# ANSI_Mono_vid_board.net
KiCad netlist of a schematic drawn in EAGLE
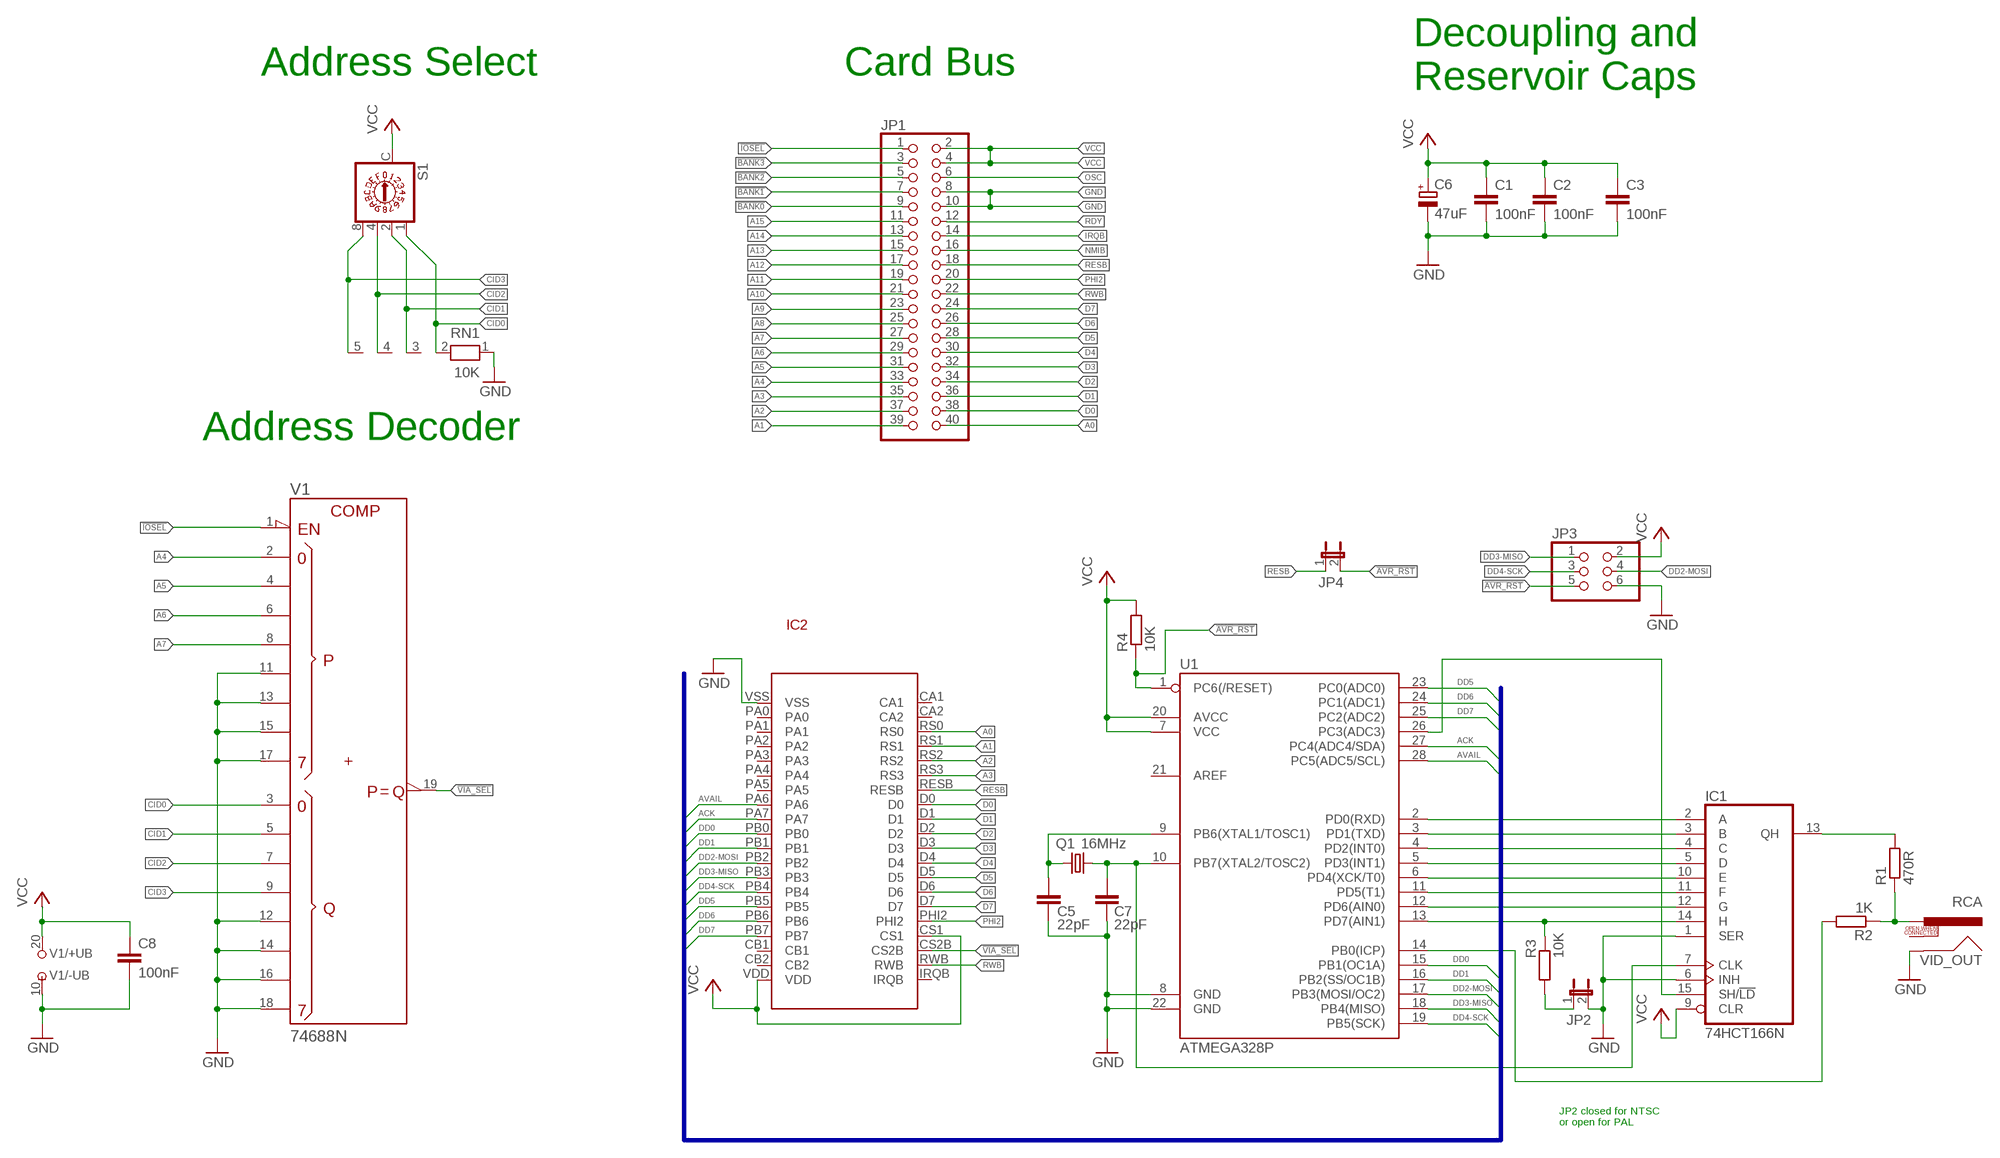
[diagram p0: schematic, sheet 1]

(export (version "E")
  (design (tool "Eeschema 10.0.6"))
  (components
    (comp (ref "C1")
      (value "100nF")
      (footprint "eagle-import:C050-025X075")
      (libsource (lib "eagle-import") (part "C-EU050-025X075"))
    )
    (comp (ref "C2")
      (value "100nF")
      (footprint "eagle-import:C050-025X075")
      (libsource (lib "eagle-import") (part "C-EU050-025X075"))
    )
    (comp (ref "C3")
      (value "100nF")
      (footprint "eagle-import:C025-025X050")
      (libsource (lib "eagle-import") (part "C-EU025-025X050"))
    )
    (comp (ref "C5")
      (value "22pF")
      (footprint "eagle-import:C050-025X075")
      (libsource (lib "eagle-import") (part "C-EU050-025X075"))
    )
    (comp (ref "C6")
      (value "47uF")
      (footprint "eagle-import:E2,5-7")
      (libsource (lib "eagle-import") (part "CPOL-EUE2.5-7"))
    )
    (comp (ref "C7")
      (value "22pF")
      (footprint "eagle-import:C050-025X075")
      (libsource (lib "eagle-import") (part "C-EU050-025X075"))
    )
    (comp (ref "C8")
      (value "100nF")
      (footprint "eagle-import:C050-025X075")
      (libsource (lib "eagle-import") (part "C-EU050-025X075"))
    )
    (comp (ref "IC1")
      (value "74HCT166N")
      (footprint "eagle-import:DIL16")
      (libsource (lib "eagle-import") (part "74166NHCT"))
    )
    (comp (ref "IC2")
      (value "W65C22")
      (footprint "eagle-import:W65C22-DIP")
      (libsource (lib "eagle-import") (part "W65C22"))
    )
    (comp (ref "JP1")
      (value "PINHD-2X20/90")
      (footprint "eagle-import:2X20_90")
      (libsource (lib "eagle-import") (part "PINHD-2X20/90"))
    )
    (comp (ref "JP2")
      (value "JP1E")
      (footprint "eagle-import:JP1")
      (libsource (lib "eagle-import") (part "JP1E"))
    )
    (comp (ref "JP3")
      (value "PINHD-2X3")
      (footprint "eagle-import:2X03")
      (libsource (lib "eagle-import") (part "PINHD-2X3"))
    )
    (comp (ref "JP4")
      (value "JP1E")
      (footprint "eagle-import:JP1")
      (libsource (lib "eagle-import") (part "JP1E"))
    )
    (comp (ref "Q1")
      (value "16MHz")
      (footprint "eagle-import:HC49U-V")
      (libsource (lib "eagle-import") (part "CRYSTALHC49U-V"))
    )
    (comp (ref "R1")
      (value "470R")
      (footprint "eagle-import:0207_10")
      (libsource (lib "eagle-import") (part "R-EU_0207/10"))
    )
    (comp (ref "R2")
      (value "1K")
      (footprint "eagle-import:0207_10")
      (libsource (lib "eagle-import") (part "R-EU_0207/10"))
    )
    (comp (ref "R3")
      (value "10K")
      (footprint "eagle-import:0207_2V")
      (libsource (lib "eagle-import") (part "R-EU_0207/2V"))
    )
    (comp (ref "R4")
      (value "10K")
      (footprint "eagle-import:0207_7")
      (libsource (lib "eagle-import") (part "R-EU_0207/7"))
    )
    (comp (ref "RN1")
      (value "10K")
      (footprint "eagle-import:RN-5")
      (libsource (lib "eagle-import") (part "RN04"))
    )
    (comp (ref "S1")
      (value "DRR3016")
      (footprint "eagle-import:DRR3010")
      (libsource (lib "eagle-import") (part "DRR3016"))
    )
    (comp (ref "U1")
      (value "ATMEGA328P")
      (footprint "eagle-import:DIL28-3")
      (libsource (lib "eagle-import") (part "ATMEGA328P_PDIP"))
    )
    (comp (ref "V1")
      (value "74688N")
      (footprint "eagle-import:DIL20")
      (libsource (lib "eagle-import") (part "74688N"))
    )
    (comp (ref "VID_OUT")
      (value "RCA")
      (footprint "eagle-import:RCA")
      (libsource (lib "eagle-import") (part "RCA"))
    )
  )
  (nets
    (net (code "1") (name "/ACK") (class "Default")
      (node (ref "IC2") (pin "PA7") (pinfunction "PA7_PA7") (pintype "bidirectional"))
      (node (ref "U1") (pin "27") (pinfunction "PC4(ADC4/SDA)_27") (pintype "bidirectional"))
    )
    (net (code "2") (name "/AVAIL") (class "Default")
      (node (ref "IC2") (pin "PA6") (pinfunction "PA6_PA6") (pintype "bidirectional"))
      (node (ref "U1") (pin "28") (pinfunction "PC5(ADC5/SCL)_28") (pintype "bidirectional"))
    )
    (net (code "3") (name "/DD0") (class "Default")
      (node (ref "IC2") (pin "PB0") (pinfunction "PB0_PB0") (pintype "bidirectional"))
      (node (ref "U1") (pin "15") (pinfunction "PB1(OC1A)_15") (pintype "bidirectional"))
    )
    (net (code "4") (name "/DD1") (class "Default")
      (node (ref "IC2") (pin "PB1") (pinfunction "PB1_PB1") (pintype "bidirectional"))
      (node (ref "U1") (pin "16") (pinfunction "PB2(SS/OC1B)_16") (pintype "bidirectional"))
    )
    (net (code "5") (name "/DD5") (class "Default")
      (node (ref "IC2") (pin "PB5") (pinfunction "PB5_PB5") (pintype "bidirectional"))
      (node (ref "U1") (pin "23") (pinfunction "PC0(ADC0)_23") (pintype "bidirectional"))
    )
    (net (code "6") (name "/DD6") (class "Default")
      (node (ref "IC2") (pin "PB6") (pinfunction "PB6_PB6") (pintype "bidirectional"))
      (node (ref "U1") (pin "24") (pinfunction "PC1(ADC1)_24") (pintype "bidirectional"))
    )
    (net (code "7") (name "/DD7") (class "Default")
      (node (ref "IC2") (pin "PB7") (pinfunction "PB7_PB7") (pintype "bidirectional"))
      (node (ref "U1") (pin "25") (pinfunction "PC2(ADC2)_25") (pintype "bidirectional"))
    )
    (net (code "8") (name "/~{AVR_RST}") (class "Default")
      (node (ref "JP3") (pin "5") (pinfunction "5_5") (pintype "passive"))
      (node (ref "JP4") (pin "2") (pinfunction "2_2") (pintype "passive"))
      (node (ref "R4") (pin "1") (pinfunction "1_1") (pintype "passive"))
      (node (ref "U1") (pin "1") (pinfunction "PC6(/RESET)_1") (pintype "bidirectional"))
    )
    (net (code "9") (name "/~{BANK0}") (class "Default")
      (node (ref "JP1") (pin "9") (pinfunction "9_9") (pintype "passive"))
    )
    (net (code "10") (name "/~{BANK1}") (class "Default")
      (node (ref "JP1") (pin "7") (pinfunction "7_7") (pintype "passive"))
    )
    (net (code "11") (name "/~{BANK2}") (class "Default")
      (node (ref "JP1") (pin "5") (pinfunction "5_5") (pintype "passive"))
    )
    (net (code "12") (name "/~{BANK3}") (class "Default")
      (node (ref "JP1") (pin "3") (pinfunction "3_3") (pintype "passive"))
    )
    (net (code "13") (name "/~{IOSEL}") (class "Default")
      (node (ref "JP1") (pin "1") (pinfunction "1_1") (pintype "passive"))
      (node (ref "V1") (pin "1") (pinfunction "~{G}_1") (pintype "input"))
    )
    (net (code "14") (name "/~{VIA_SEL}") (class "Default")
      (node (ref "IC2") (pin "CS2B") (pinfunction "CS2B_CS2B") (pintype "bidirectional"))
      (node (ref "V1") (pin "19") (pinfunction "~{P=Q}_19") (pintype "output"))
    )
    (net (code "15") (name "A0") (class "Default")
      (node (ref "IC2") (pin "RS0") (pinfunction "RS0_RS0") (pintype "input"))
      (node (ref "JP1") (pin "40") (pinfunction "40_40") (pintype "passive"))
    )
    (net (code "16") (name "A1") (class "Default")
      (node (ref "IC2") (pin "RS1") (pinfunction "RS1_RS1") (pintype "input"))
      (node (ref "JP1") (pin "39") (pinfunction "39_39") (pintype "passive"))
    )
    (net (code "17") (name "A2") (class "Default")
      (node (ref "IC2") (pin "RS2") (pinfunction "RS2_RS2") (pintype "input"))
      (node (ref "JP1") (pin "37") (pinfunction "37_37") (pintype "passive"))
    )
    (net (code "18") (name "A3") (class "Default")
      (node (ref "IC2") (pin "RS3") (pinfunction "RS3_RS3") (pintype "input"))
      (node (ref "JP1") (pin "35") (pinfunction "35_35") (pintype "passive"))
    )
    (net (code "19") (name "A4") (class "Default")
      (node (ref "JP1") (pin "33") (pinfunction "33_33") (pintype "passive"))
      (node (ref "V1") (pin "2") (pinfunction "P0_2") (pintype "input"))
    )
    (net (code "20") (name "A5") (class "Default")
      (node (ref "JP1") (pin "31") (pinfunction "31_31") (pintype "passive"))
      (node (ref "V1") (pin "4") (pinfunction "P1_4") (pintype "input"))
    )
    (net (code "21") (name "A6") (class "Default")
      (node (ref "JP1") (pin "29") (pinfunction "29_29") (pintype "passive"))
      (node (ref "V1") (pin "6") (pinfunction "P2_6") (pintype "input"))
    )
    (net (code "22") (name "A7") (class "Default")
      (node (ref "JP1") (pin "27") (pinfunction "27_27") (pintype "passive"))
      (node (ref "V1") (pin "8") (pinfunction "P3_8") (pintype "input"))
    )
    (net (code "23") (name "A8") (class "Default")
      (node (ref "JP1") (pin "25") (pinfunction "25_25") (pintype "passive"))
    )
    (net (code "24") (name "A9") (class "Default")
      (node (ref "JP1") (pin "23") (pinfunction "23_23") (pintype "passive"))
    )
    (net (code "25") (name "A10") (class "Default")
      (node (ref "JP1") (pin "21") (pinfunction "21_21") (pintype "passive"))
    )
    (net (code "26") (name "A11") (class "Default")
      (node (ref "JP1") (pin "19") (pinfunction "19_19") (pintype "passive"))
    )
    (net (code "27") (name "A12") (class "Default")
      (node (ref "JP1") (pin "17") (pinfunction "17_17") (pintype "passive"))
    )
    (net (code "28") (name "A13") (class "Default")
      (node (ref "JP1") (pin "15") (pinfunction "15_15") (pintype "passive"))
    )
    (net (code "29") (name "A14") (class "Default")
      (node (ref "JP1") (pin "13") (pinfunction "13_13") (pintype "passive"))
    )
    (net (code "30") (name "A15") (class "Default")
      (node (ref "JP1") (pin "11") (pinfunction "11_11") (pintype "passive"))
    )
    (net (code "31") (name "CID0") (class "Default")
      (node (ref "RN1") (pin "2") (pinfunction "2_2") (pintype "passive"))
      (node (ref "S1") (pin "1") (pinfunction "1_1") (pintype "passive"))
      (node (ref "V1") (pin "3") (pinfunction "Q0_3") (pintype "input"))
    )
    (net (code "32") (name "CID1") (class "Default")
      (node (ref "RN1") (pin "3") (pinfunction "3_3") (pintype "passive"))
      (node (ref "S1") (pin "2") (pinfunction "2_2") (pintype "passive"))
      (node (ref "V1") (pin "5") (pinfunction "Q1_5") (pintype "input"))
    )
    (net (code "33") (name "CID2") (class "Default")
      (node (ref "RN1") (pin "4") (pinfunction "4_4") (pintype "passive"))
      (node (ref "S1") (pin "4") (pinfunction "4_4") (pintype "passive"))
      (node (ref "V1") (pin "7") (pinfunction "Q2_7") (pintype "input"))
    )
    (net (code "34") (name "CID3") (class "Default")
      (node (ref "RN1") (pin "5") (pinfunction "5_5") (pintype "passive"))
      (node (ref "S1") (pin "8") (pinfunction "8_8") (pintype "passive"))
      (node (ref "V1") (pin "9") (pinfunction "Q3_9") (pintype "input"))
    )
    (net (code "35") (name "D0") (class "Default")
      (node (ref "IC2") (pin "D0") (pinfunction "D0_D0") (pintype "bidirectional"))
      (node (ref "JP1") (pin "38") (pinfunction "38_38") (pintype "passive"))
    )
    (net (code "36") (name "D1") (class "Default")
      (node (ref "IC2") (pin "D1") (pinfunction "D1_D1") (pintype "bidirectional"))
      (node (ref "JP1") (pin "36") (pinfunction "36_36") (pintype "passive"))
    )
    (net (code "37") (name "D2") (class "Default")
      (node (ref "IC2") (pin "D2") (pinfunction "D2_D2") (pintype "bidirectional"))
      (node (ref "JP1") (pin "34") (pinfunction "34_34") (pintype "passive"))
    )
    (net (code "38") (name "D3") (class "Default")
      (node (ref "IC2") (pin "D3") (pinfunction "D3_D3") (pintype "bidirectional"))
      (node (ref "JP1") (pin "32") (pinfunction "32_32") (pintype "passive"))
    )
    (net (code "39") (name "D4") (class "Default")
      (node (ref "IC2") (pin "D4") (pinfunction "D4_D4") (pintype "bidirectional"))
      (node (ref "JP1") (pin "30") (pinfunction "30_30") (pintype "passive"))
    )
    (net (code "40") (name "D5") (class "Default")
      (node (ref "IC2") (pin "D5") (pinfunction "D5_D5") (pintype "bidirectional"))
      (node (ref "JP1") (pin "28") (pinfunction "28_28") (pintype "passive"))
    )
    (net (code "41") (name "D6") (class "Default")
      (node (ref "IC2") (pin "D6") (pinfunction "D6_D6") (pintype "bidirectional"))
      (node (ref "JP1") (pin "26") (pinfunction "26_26") (pintype "passive"))
    )
    (net (code "42") (name "D7") (class "Default")
      (node (ref "IC2") (pin "D7") (pinfunction "D7_D7") (pintype "bidirectional"))
      (node (ref "JP1") (pin "24") (pinfunction "24_24") (pintype "passive"))
    )
    (net (code "43") (name "DD2-MOSI") (class "Default")
      (node (ref "IC2") (pin "PB2") (pinfunction "PB2_PB2") (pintype "bidirectional"))
      (node (ref "JP3") (pin "4") (pinfunction "4_4") (pintype "passive"))
      (node (ref "U1") (pin "17") (pinfunction "PB3(MOSI/OC2)_17") (pintype "bidirectional"))
    )
    (net (code "44") (name "DD3-MISO") (class "Default")
      (node (ref "IC2") (pin "PB3") (pinfunction "PB3_PB3") (pintype "bidirectional"))
      (node (ref "JP3") (pin "1") (pinfunction "1_1") (pintype "passive"))
      (node (ref "U1") (pin "18") (pinfunction "PB4(MISO)_18") (pintype "bidirectional"))
    )
    (net (code "45") (name "DD4-SCK") (class "Default")
      (node (ref "IC2") (pin "PB4") (pinfunction "PB4_PB4") (pintype "bidirectional"))
      (node (ref "JP3") (pin "3") (pinfunction "3_3") (pintype "passive"))
      (node (ref "U1") (pin "19") (pinfunction "PB5(SCK)_19") (pintype "bidirectional"))
    )
    (net (code "46") (name "GND") (class "Default")
      (node (ref "C1") (pin "2") (pinfunction "2_2") (pintype "passive"))
      (node (ref "C2") (pin "2") (pinfunction "2_2") (pintype "passive"))
      (node (ref "C3") (pin "2") (pinfunction "2_2") (pintype "passive"))
      (node (ref "C5") (pin "2") (pinfunction "2_2") (pintype "passive"))
      (node (ref "C6") (pin "-") (pinfunction "-_-") (pintype "passive"))
      (node (ref "C7") (pin "2") (pinfunction "2_2") (pintype "passive"))
      (node (ref "C8") (pin "2") (pinfunction "2_2") (pintype "passive"))
      (node (ref "IC1") (pin "1") (pinfunction "SER_1") (pintype "input"))
      (node (ref "IC1") (pin "6") (pinfunction "INH_6") (pintype "input"))
      (node (ref "IC2") (pin "VSS") (pinfunction "VSS_VSS") (pintype "power_in"))
      (node (ref "JP1") (pin "10") (pinfunction "10_10") (pintype "passive"))
      (node (ref "JP1") (pin "8") (pinfunction "8_8") (pintype "passive"))
      (node (ref "JP2") (pin "2") (pinfunction "2_2") (pintype "passive"))
      (node (ref "JP3") (pin "6") (pinfunction "6_6") (pintype "passive"))
      (node (ref "RN1") (pin "1") (pinfunction "1_1") (pintype "passive"))
      (node (ref "U1") (pin "22") (pinfunction "GND_22") (pintype "bidirectional"))
      (node (ref "U1") (pin "8") (pinfunction "GND_8") (pintype "bidirectional"))
      (node (ref "V1") (pin "10") (pinfunction "-UB_10") (pintype "power_in"))
      (node (ref "V1") (pin "11") (pinfunction "P4_11") (pintype "input"))
      (node (ref "V1") (pin "12") (pinfunction "Q4_12") (pintype "input"))
      (node (ref "V1") (pin "13") (pinfunction "P5_13") (pintype "input"))
      (node (ref "V1") (pin "14") (pinfunction "Q5_14") (pintype "input"))
      (node (ref "V1") (pin "15") (pinfunction "P6_15") (pintype "input"))
      (node (ref "V1") (pin "16") (pinfunction "Q6_16") (pintype "input"))
      (node (ref "V1") (pin "17") (pinfunction "P7_17") (pintype "input"))
      (node (ref "V1") (pin "18") (pinfunction "Q7_18") (pintype "input"))
      (node (ref "VID_OUT") (pin "SHELL") (pinfunction "SHELL_SHELL") (pintype "bidirectional"))
    )
    (net (code "47") (name "IRQB") (class "Default")
      (node (ref "JP1") (pin "14") (pinfunction "14_14") (pintype "passive"))
    )
    (net (code "48") (name "NMIB") (class "Default")
      (node (ref "JP1") (pin "16") (pinfunction "16_16") (pintype "passive"))
    )
    (net (code "49") (name "Net-(IC1A-A)") (class "Default")
      (node (ref "IC1") (pin "2") (pinfunction "A_2") (pintype "input"))
      (node (ref "U1") (pin "2") (pinfunction "PD0(RXD)_2") (pintype "bidirectional"))
    )
    (net (code "50") (name "Net-(IC1A-B)") (class "Default")
      (node (ref "IC1") (pin "3") (pinfunction "B_3") (pintype "input"))
      (node (ref "U1") (pin "3") (pinfunction "PD1(TXD)_3") (pintype "bidirectional"))
    )
    (net (code "51") (name "Net-(IC1A-C)") (class "Default")
      (node (ref "IC1") (pin "4") (pinfunction "C_4") (pintype "input"))
      (node (ref "U1") (pin "4") (pinfunction "PD2(INT0)_4") (pintype "bidirectional"))
    )
    (net (code "52") (name "Net-(IC1A-CLK)") (class "Default")
      (node (ref "C7") (pin "1") (pinfunction "1_1") (pintype "passive"))
      (node (ref "IC1") (pin "7") (pinfunction "CLK_7") (pintype "input"))
      (node (ref "Q1") (pin "1") (pinfunction "1_1") (pintype "passive"))
      (node (ref "U1") (pin "10") (pinfunction "PB7(XTAL2/TOSC2)_10") (pintype "bidirectional"))
    )
    (net (code "53") (name "Net-(IC1A-D)") (class "Default")
      (node (ref "IC1") (pin "5") (pinfunction "D_5") (pintype "input"))
      (node (ref "U1") (pin "5") (pinfunction "PD3(INT1)_5") (pintype "bidirectional"))
    )
    (net (code "54") (name "Net-(IC1A-E)") (class "Default")
      (node (ref "IC1") (pin "10") (pinfunction "E_10") (pintype "input"))
      (node (ref "U1") (pin "6") (pinfunction "PD4(XCK/T0)_6") (pintype "bidirectional"))
    )
    (net (code "55") (name "Net-(IC1A-F)") (class "Default")
      (node (ref "IC1") (pin "11") (pinfunction "F_11") (pintype "input"))
      (node (ref "U1") (pin "11") (pinfunction "PD5(T1)_11") (pintype "bidirectional"))
    )
    (net (code "56") (name "Net-(IC1A-G)") (class "Default")
      (node (ref "IC1") (pin "12") (pinfunction "G_12") (pintype "input"))
      (node (ref "U1") (pin "12") (pinfunction "PD6(AIN0)_12") (pintype "bidirectional"))
    )
    (net (code "57") (name "Net-(IC1A-H)") (class "Default")
      (node (ref "IC1") (pin "14") (pinfunction "H_14") (pintype "input"))
      (node (ref "R3") (pin "2") (pinfunction "2_2") (pintype "passive"))
      (node (ref "U1") (pin "13") (pinfunction "PD7(AIN1)_13") (pintype "bidirectional"))
    )
    (net (code "58") (name "Net-(IC1A-QH)") (class "Default")
      (node (ref "IC1") (pin "13") (pinfunction "QH_13") (pintype "output"))
      (node (ref "R1") (pin "2") (pinfunction "2_2") (pintype "passive"))
    )
    (net (code "59") (name "Net-(IC1A-SH{slash}~{LD})") (class "Default")
      (node (ref "IC1") (pin "15") (pinfunction "SH/~{LD}_15") (pintype "input"))
      (node (ref "U1") (pin "26") (pinfunction "PC3(ADC3)_26") (pintype "bidirectional"))
    )
    (net (code "60") (name "Net-(JP2-Pad1)") (class "Default")
      (node (ref "JP2") (pin "1") (pinfunction "1_1") (pintype "passive"))
      (node (ref "R3") (pin "1") (pinfunction "1_1") (pintype "passive"))
    )
    (net (code "61") (name "Net-(R1-Pad1)") (class "Default")
      (node (ref "R1") (pin "1") (pinfunction "1_1") (pintype "passive"))
      (node (ref "R2") (pin "1") (pinfunction "1_1") (pintype "passive"))
      (node (ref "VID_OUT") (pin "PIN") (pinfunction "PIN_PIN") (pintype "bidirectional"))
    )
    (net (code "62") (name "Net-(U1-PB0(ICP))") (class "Default")
      (node (ref "R2") (pin "2") (pinfunction "2_2") (pintype "passive"))
      (node (ref "U1") (pin "14") (pinfunction "PB0(ICP)_14") (pintype "bidirectional"))
    )
    (net (code "63") (name "Net-(U1-PB6(XTAL1{slash}TOSC1))") (class "Default")
      (node (ref "C5") (pin "1") (pinfunction "1_1") (pintype "passive"))
      (node (ref "Q1") (pin "2") (pinfunction "2_2") (pintype "passive"))
      (node (ref "U1") (pin "9") (pinfunction "PB6(XTAL1/TOSC1)_9") (pintype "bidirectional"))
    )
    (net (code "64") (name "OSC") (class "Default")
      (node (ref "JP1") (pin "6") (pinfunction "6_6") (pintype "passive"))
    )
    (net (code "65") (name "PHI2") (class "Default")
      (node (ref "IC2") (pin "PHI2") (pinfunction "PHI2_PHI2") (pintype "input"))
      (node (ref "JP1") (pin "20") (pinfunction "20_20") (pintype "passive"))
    )
    (net (code "66") (name "RDY") (class "Default")
      (node (ref "JP1") (pin "12") (pinfunction "12_12") (pintype "passive"))
    )
    (net (code "67") (name "RESB") (class "Default")
      (node (ref "IC2") (pin "RESB") (pinfunction "RESB_RESB") (pintype "input"))
      (node (ref "JP1") (pin "18") (pinfunction "18_18") (pintype "passive"))
      (node (ref "JP4") (pin "1") (pinfunction "1_1") (pintype "passive"))
    )
    (net (code "68") (name "RWB") (class "Default")
      (node (ref "IC2") (pin "RWB") (pinfunction "RWB_RWB") (pintype "input"))
      (node (ref "JP1") (pin "22") (pinfunction "22_22") (pintype "passive"))
    )
    (net (code "69") (name "VCC") (class "Default")
      (node (ref "C1") (pin "1") (pinfunction "1_1") (pintype "passive"))
      (node (ref "C2") (pin "1") (pinfunction "1_1") (pintype "passive"))
      (node (ref "C3") (pin "1") (pinfunction "1_1") (pintype "passive"))
      (node (ref "C6") (pin "+") (pinfunction "+_+") (pintype "passive"))
      (node (ref "C8") (pin "1") (pinfunction "1_1") (pintype "passive"))
      (node (ref "IC1") (pin "9") (pinfunction "CLR_9") (pintype "input"))
      (node (ref "IC2") (pin "CS1") (pinfunction "CS1_CS1") (pintype "bidirectional"))
      (node (ref "IC2") (pin "VDD") (pinfunction "VDD_VDD") (pintype "power_in"))
      (node (ref "JP1") (pin "2") (pinfunction "2_2") (pintype "passive"))
      (node (ref "JP1") (pin "4") (pinfunction "4_4") (pintype "passive"))
      (node (ref "JP3") (pin "2") (pinfunction "2_2") (pintype "passive"))
      (node (ref "R4") (pin "2") (pinfunction "2_2") (pintype "passive"))
      (node (ref "S1") (pin "C") (pinfunction "C_C") (pintype "passive"))
      (node (ref "U1") (pin "20") (pinfunction "AVCC_20") (pintype "bidirectional"))
      (node (ref "U1") (pin "7") (pinfunction "VCC_7") (pintype "bidirectional"))
      (node (ref "V1") (pin "20") (pinfunction "+UB_20") (pintype "power_in"))
    )
    (net (code "70") (name "unconnected-(IC2-PadCA1)") (class "Default")
      (node (ref "IC2") (pin "CA1") (pinfunction "CA1_CA1") (pintype "bidirectional"))
    )
    (net (code "71") (name "unconnected-(IC2-PadCA2)") (class "Default")
      (node (ref "IC2") (pin "CA2") (pinfunction "CA2_CA2") (pintype "bidirectional"))
    )
    (net (code "72") (name "unconnected-(IC2-PadCB1)") (class "Default")
      (node (ref "IC2") (pin "CB1") (pinfunction "CB1_CB1") (pintype "bidirectional"))
    )
    (net (code "73") (name "unconnected-(IC2-PadCB2)") (class "Default")
      (node (ref "IC2") (pin "CB2") (pinfunction "CB2_CB2") (pintype "bidirectional"))
    )
    (net (code "74") (name "unconnected-(IC2-PadIRQB)") (class "Default")
      (node (ref "IC2") (pin "IRQB") (pinfunction "IRQB_IRQB") (pintype "output"))
    )
    (net (code "75") (name "unconnected-(IC2-PadPA0)") (class "Default")
      (node (ref "IC2") (pin "PA0") (pinfunction "PA0_PA0") (pintype "bidirectional"))
    )
    (net (code "76") (name "unconnected-(IC2-PadPA1)") (class "Default")
      (node (ref "IC2") (pin "PA1") (pinfunction "PA1_PA1") (pintype "bidirectional"))
    )
    (net (code "77") (name "unconnected-(IC2-PadPA2)") (class "Default")
      (node (ref "IC2") (pin "PA2") (pinfunction "PA2_PA2") (pintype "bidirectional"))
    )
    (net (code "78") (name "unconnected-(IC2-PadPA3)") (class "Default")
      (node (ref "IC2") (pin "PA3") (pinfunction "PA3_PA3") (pintype "bidirectional"))
    )
    (net (code "79") (name "unconnected-(IC2-PadPA4)") (class "Default")
      (node (ref "IC2") (pin "PA4") (pinfunction "PA4_PA4") (pintype "bidirectional"))
    )
    (net (code "80") (name "unconnected-(IC2-PadPA5)") (class "Default")
      (node (ref "IC2") (pin "PA5") (pinfunction "PA5_PA5") (pintype "bidirectional"))
    )
    (net (code "81") (name "unconnected-(U1-AREF-Pad21)") (class "Default")
      (node (ref "U1") (pin "21") (pinfunction "AREF_21") (pintype "bidirectional"))
    )
    (net (code "82") (name "unconnected-(VID_OUT-PadSWITCH)") (class "Default")
      (node (ref "VID_OUT") (pin "SWITCH") (pinfunction "SWITCH_SWITCH") (pintype "bidirectional"))
    )
  )
)
